# icehax40.net
KiCad netlist of a schematic drawn in EAGLE
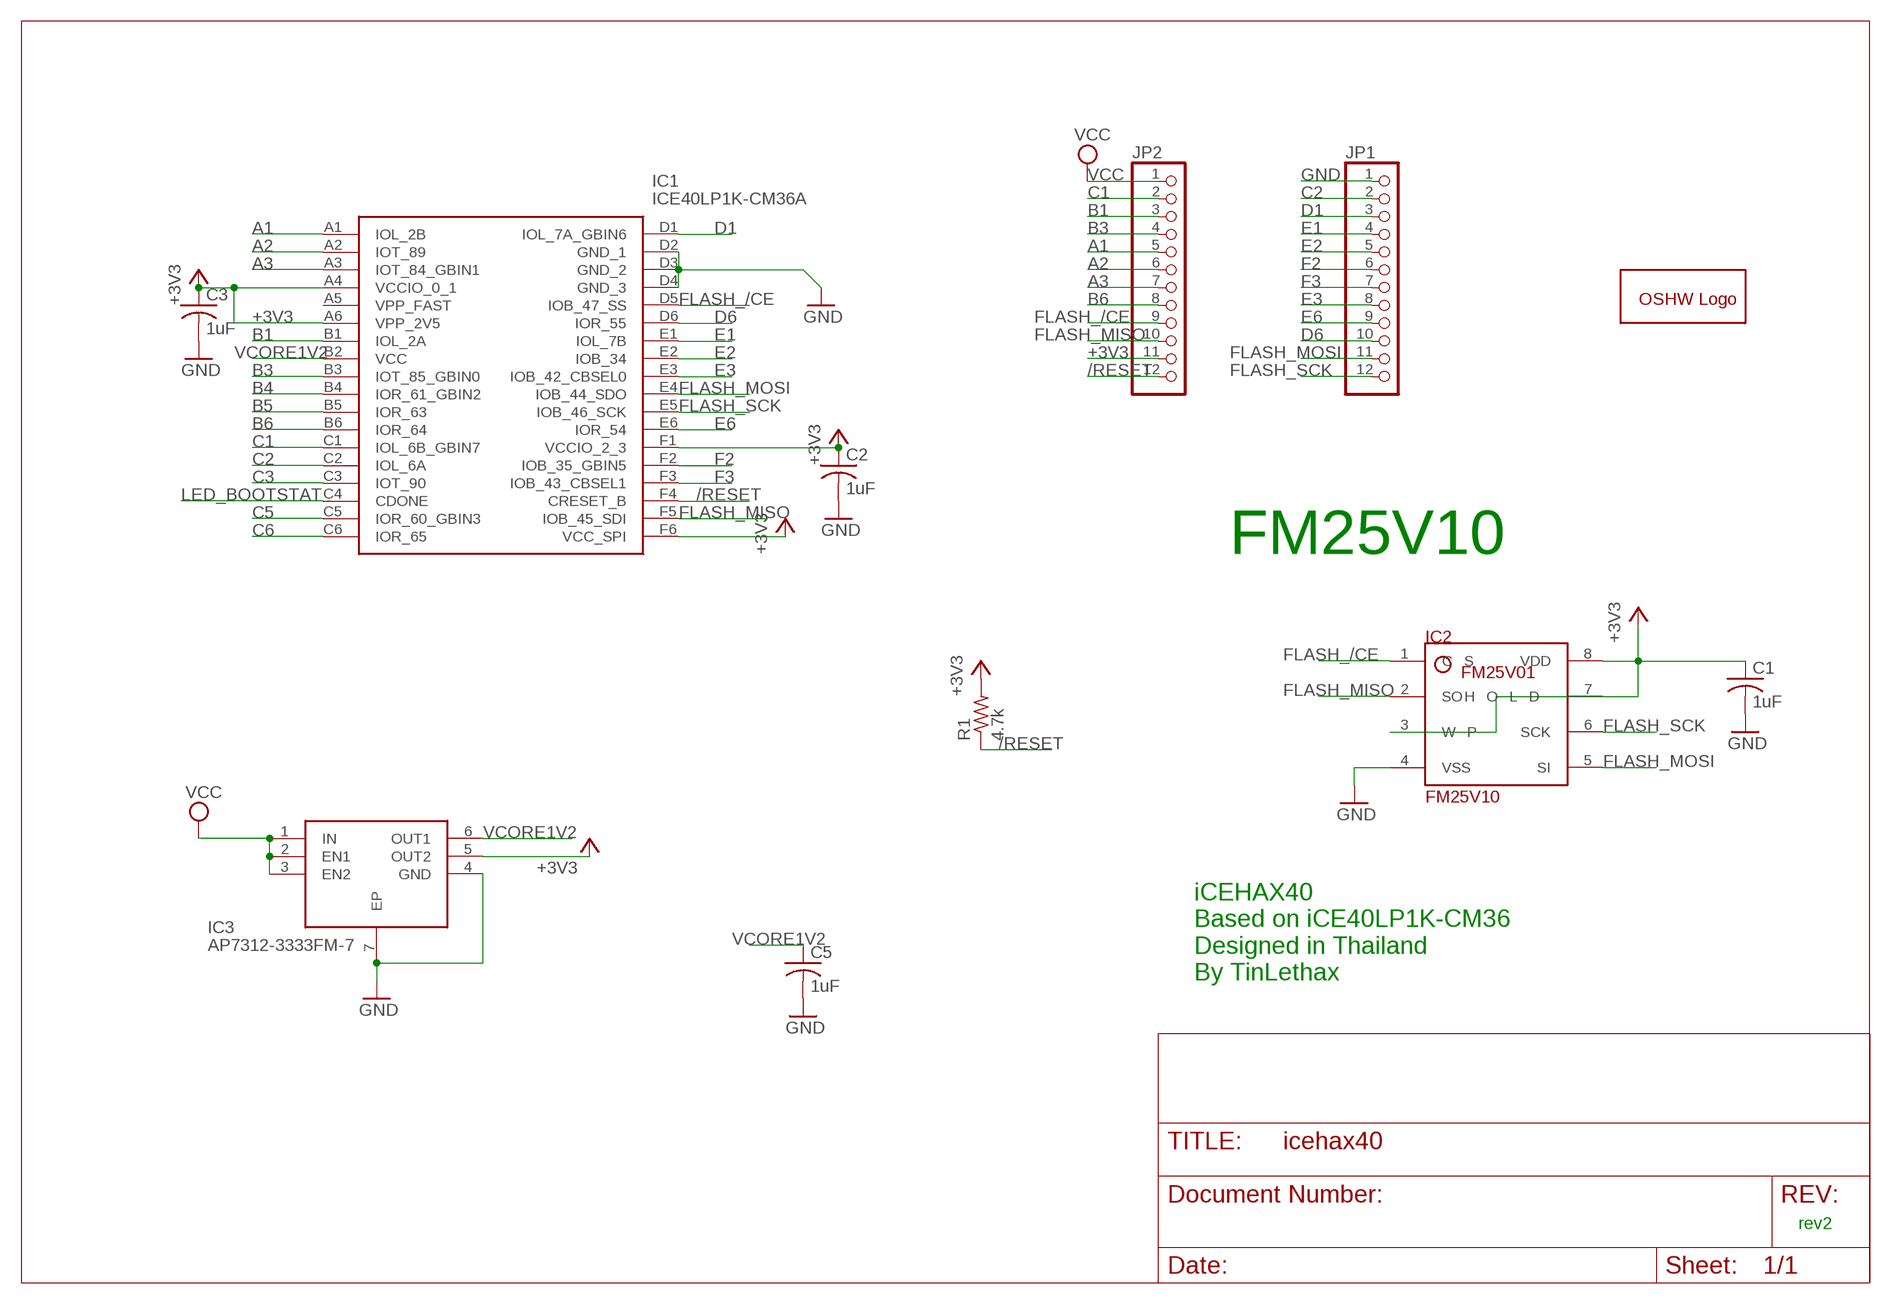
[diagram p0: schematic, sheet 1]

(export (version "E")
  (design (tool "Eeschema 10.0.6"))
  (components
    (comp (ref "C1")
      (value "1uF")
      (footprint "eagle-import:C0603")
      (libsource (lib "eagle-import") (part "C-USC0603"))
    )
    (comp (ref "C2")
      (value "1uF")
      (footprint "eagle-import:C0603")
      (libsource (lib "eagle-import") (part "C-USC0603"))
    )
    (comp (ref "C3")
      (value "1uF")
      (footprint "eagle-import:C0603")
      (libsource (lib "eagle-import") (part "C-USC0603"))
    )
    (comp (ref "C5")
      (value "1uF")
      (footprint "eagle-import:C0603")
      (libsource (lib "eagle-import") (part "C-USC0603"))
    )
    (comp (ref "GOLD_ORB_SM1")
      (value "OSHWLOGOLOGO5MM")
      (footprint "eagle-import:OSHW_5MM")
      (libsource (lib "eagle-import") (part "OSHWLOGOLOGO5MM"))
    )
    (comp (ref "IC1")
      (value "ICE40LP1K-CM36A")
      (footprint "eagle-import:BGA36C40P6X6_250X250X100")
      (fields (field (name "MOUSER_PART_NUMBER") "842-ICE40LP1K-CM36A"))
      (libsource (lib "eagle-import") (part "ICE40LP1K-CM36A"))
    )
    (comp (ref "IC2")
      (value "FM25V10")
      (footprint "eagle-import:SOIC127P601X172-8N")
      (fields (field (name "PARTNO") "FM52V01"))
      (libsource (lib "eagle-import") (part "FM25V01"))
    )
    (comp (ref "IC3")
      (value "AP7312-3333FM-7")
      (footprint "eagle-import:SON50P201X181X60-7N")
      (fields (field (name "MOUSER_PART_NUMBER") "621-AP7312-3333FM-7"))
      (libsource (lib "eagle-import") (part "AP7312-3333FM-7"))
    )
    (comp (ref "JP1")
      (value "PINHD-1X12")
      (footprint "eagle-import:1X12")
      (libsource (lib "eagle-import") (part "PINHD-1X12"))
    )
    (comp (ref "JP2")
      (value "PINHD-1X12")
      (footprint "eagle-import:1X12")
      (libsource (lib "eagle-import") (part "PINHD-1X12"))
    )
    (comp (ref "R1")
      (value "4.7k")
      (footprint "eagle-import:R0603")
      (libsource (lib "eagle-import") (part "R-US_R0603"))
    )
  )
  (nets
    (net (code "1") (name "+3V3") (class "Default")
      (node (ref "C1") (pin "1") (pinfunction "1_1") (pintype "passive"))
      (node (ref "C2") (pin "1") (pinfunction "1_1") (pintype "passive"))
      (node (ref "C3") (pin "1") (pinfunction "1_1") (pintype "passive"))
      (node (ref "IC1") (pin "A4") (pinfunction "VCCIO_0_1_A4") (pintype "bidirectional"))
      (node (ref "IC1") (pin "A6") (pinfunction "VPP_2V5_A6") (pintype "bidirectional"))
      (node (ref "IC1") (pin "F1") (pinfunction "VCCIO_2_3_F1") (pintype "bidirectional"))
      (node (ref "IC1") (pin "F6") (pinfunction "VCC_SPI_F6") (pintype "bidirectional"))
      (node (ref "IC2") (pin "3") (pinfunction "W̅P̅_3") (pintype "bidirectional"))
      (node (ref "IC2") (pin "7") (pinfunction "H̅O̅L̅D̅_7") (pintype "bidirectional"))
      (node (ref "IC2") (pin "8") (pinfunction "VDD_8") (pintype "bidirectional"))
      (node (ref "IC3") (pin "5") (pinfunction "OUT2_5") (pintype "bidirectional"))
      (node (ref "JP2") (pin "11") (pinfunction "11_11") (pintype "passive"))
      (node (ref "R1") (pin "2") (pinfunction "2_2") (pintype "passive"))
    )
    (net (code "2") (name "/A1") (class "Default")
      (node (ref "IC1") (pin "A1") (pinfunction "IOL_2B_A1") (pintype "bidirectional"))
      (node (ref "JP2") (pin "5") (pinfunction "5_5") (pintype "passive"))
    )
    (net (code "3") (name "/A2") (class "Default")
      (node (ref "IC1") (pin "A2") (pinfunction "IOT_89_A2") (pintype "bidirectional"))
      (node (ref "JP2") (pin "6") (pinfunction "6_6") (pintype "passive"))
    )
    (net (code "4") (name "/A3") (class "Default")
      (node (ref "IC1") (pin "A3") (pinfunction "IOT_84_GBIN1_A3") (pintype "bidirectional"))
      (node (ref "JP2") (pin "7") (pinfunction "7_7") (pintype "passive"))
    )
    (net (code "5") (name "/B1") (class "Default")
      (node (ref "IC1") (pin "B1") (pinfunction "IOL_2A_B1") (pintype "bidirectional"))
      (node (ref "JP2") (pin "3") (pinfunction "3_3") (pintype "passive"))
    )
    (net (code "6") (name "/B3") (class "Default")
      (node (ref "IC1") (pin "B3") (pinfunction "IOT_85_GBIN0_B3") (pintype "bidirectional"))
      (node (ref "JP2") (pin "4") (pinfunction "4_4") (pintype "passive"))
    )
    (net (code "7") (name "/B4") (class "Default")
      (node (ref "IC1") (pin "B4") (pinfunction "IOR_61_GBIN2_B4") (pintype "bidirectional"))
    )
    (net (code "8") (name "/B5") (class "Default")
      (node (ref "IC1") (pin "B5") (pinfunction "IOR_63_B5") (pintype "bidirectional"))
    )
    (net (code "9") (name "/B6") (class "Default")
      (node (ref "IC1") (pin "B6") (pinfunction "IOR_64_B6") (pintype "bidirectional"))
      (node (ref "JP2") (pin "8") (pinfunction "8_8") (pintype "passive"))
    )
    (net (code "10") (name "/C1") (class "Default")
      (node (ref "IC1") (pin "C1") (pinfunction "IOL_6B_GBIN7_C1") (pintype "bidirectional"))
      (node (ref "JP2") (pin "2") (pinfunction "2_2") (pintype "passive"))
    )
    (net (code "11") (name "/C2") (class "Default")
      (node (ref "IC1") (pin "C2") (pinfunction "IOL_6A_C2") (pintype "bidirectional"))
      (node (ref "JP1") (pin "2") (pinfunction "2_2") (pintype "passive"))
    )
    (net (code "12") (name "/C3") (class "Default")
      (node (ref "IC1") (pin "C3") (pinfunction "IOT_90_C3") (pintype "bidirectional"))
    )
    (net (code "13") (name "/C5") (class "Default")
      (node (ref "IC1") (pin "C5") (pinfunction "IOR_60_GBIN3_C5") (pintype "bidirectional"))
    )
    (net (code "14") (name "/C6") (class "Default")
      (node (ref "IC1") (pin "C6") (pinfunction "IOR_65_C6") (pintype "bidirectional"))
    )
    (net (code "15") (name "/D1") (class "Default")
      (node (ref "IC1") (pin "D1") (pinfunction "IOL_7A_GBIN6_D1") (pintype "bidirectional"))
      (node (ref "JP1") (pin "3") (pinfunction "3_3") (pintype "passive"))
    )
    (net (code "16") (name "/D6") (class "Default")
      (node (ref "IC1") (pin "D6") (pinfunction "IOR_55_D6") (pintype "bidirectional"))
      (node (ref "JP1") (pin "10") (pinfunction "10_10") (pintype "passive"))
    )
    (net (code "17") (name "/E1") (class "Default")
      (node (ref "IC1") (pin "E1") (pinfunction "IOL_7B_E1") (pintype "bidirectional"))
      (node (ref "JP1") (pin "4") (pinfunction "4_4") (pintype "passive"))
    )
    (net (code "18") (name "/E2") (class "Default")
      (node (ref "IC1") (pin "E2") (pinfunction "IOB_34_E2") (pintype "bidirectional"))
      (node (ref "JP1") (pin "5") (pinfunction "5_5") (pintype "passive"))
    )
    (net (code "19") (name "/E3") (class "Default")
      (node (ref "IC1") (pin "E3") (pinfunction "IOB_42_CBSEL0_E3") (pintype "bidirectional"))
      (node (ref "JP1") (pin "8") (pinfunction "8_8") (pintype "passive"))
    )
    (net (code "20") (name "/E6") (class "Default")
      (node (ref "IC1") (pin "E6") (pinfunction "IOR_54_E6") (pintype "bidirectional"))
      (node (ref "JP1") (pin "9") (pinfunction "9_9") (pintype "passive"))
    )
    (net (code "21") (name "/F2") (class "Default")
      (node (ref "IC1") (pin "F2") (pinfunction "IOB_35_GBIN5_F2") (pintype "bidirectional"))
      (node (ref "JP1") (pin "6") (pinfunction "6_6") (pintype "passive"))
    )
    (net (code "22") (name "/F3") (class "Default")
      (node (ref "IC1") (pin "F3") (pinfunction "IOB_43_CBSEL1_F3") (pintype "bidirectional"))
      (node (ref "JP1") (pin "7") (pinfunction "7_7") (pintype "passive"))
    )
    (net (code "23") (name "/FLASH_MISO") (class "Default")
      (node (ref "IC1") (pin "F5") (pinfunction "IOB_45_SDI_F5") (pintype "bidirectional"))
      (node (ref "IC2") (pin "2") (pinfunction "SO_2") (pintype "bidirectional"))
      (node (ref "JP2") (pin "10") (pinfunction "10_10") (pintype "passive"))
    )
    (net (code "24") (name "/FLASH_MOSI") (class "Default")
      (node (ref "IC1") (pin "E4") (pinfunction "IOB_44_SDO_E4") (pintype "bidirectional"))
      (node (ref "IC2") (pin "5") (pinfunction "SI_5") (pintype "bidirectional"))
      (node (ref "JP1") (pin "11") (pinfunction "11_11") (pintype "passive"))
    )
    (net (code "25") (name "/FLASH_SCK") (class "Default")
      (node (ref "IC1") (pin "E5") (pinfunction "IOB_46_SCK_E5") (pintype "bidirectional"))
      (node (ref "IC2") (pin "6") (pinfunction "SCK_6") (pintype "bidirectional"))
      (node (ref "JP1") (pin "12") (pinfunction "12_12") (pintype "passive"))
    )
    (net (code "26") (name "/FLASH_{slash}CE") (class "Default")
      (node (ref "IC1") (pin "D5") (pinfunction "IOB_47_SS_D5") (pintype "bidirectional"))
      (node (ref "IC2") (pin "1") (pinfunction "C̅S̅_1") (pintype "bidirectional"))
      (node (ref "JP2") (pin "9") (pinfunction "9_9") (pintype "passive"))
    )
    (net (code "27") (name "/LED_BOOTSTAT") (class "Default")
      (node (ref "IC1") (pin "C4") (pinfunction "CDONE_C4") (pintype "bidirectional"))
    )
    (net (code "28") (name "/VCORE1V2") (class "Default")
      (node (ref "C5") (pin "1") (pinfunction "1_1") (pintype "passive"))
      (node (ref "IC1") (pin "B2") (pinfunction "VCC_B2") (pintype "bidirectional"))
      (node (ref "IC3") (pin "6") (pinfunction "OUT1_6") (pintype "bidirectional"))
    )
    (net (code "29") (name "/{slash}RESET") (class "Default")
      (node (ref "IC1") (pin "F4") (pinfunction "CRESET_B_F4") (pintype "bidirectional"))
      (node (ref "JP2") (pin "12") (pinfunction "12_12") (pintype "passive"))
      (node (ref "R1") (pin "1") (pinfunction "1_1") (pintype "passive"))
    )
    (net (code "30") (name "GND") (class "Default")
      (node (ref "C1") (pin "2") (pinfunction "2_2") (pintype "passive"))
      (node (ref "C2") (pin "2") (pinfunction "2_2") (pintype "passive"))
      (node (ref "C3") (pin "2") (pinfunction "2_2") (pintype "passive"))
      (node (ref "C5") (pin "2") (pinfunction "2_2") (pintype "passive"))
      (node (ref "IC1") (pin "D2") (pinfunction "GND_1_D2") (pintype "bidirectional"))
      (node (ref "IC1") (pin "D3") (pinfunction "GND_2_D3") (pintype "bidirectional"))
      (node (ref "IC1") (pin "D4") (pinfunction "GND_3_D4") (pintype "bidirectional"))
      (node (ref "IC2") (pin "4") (pinfunction "VSS_4") (pintype "bidirectional"))
      (node (ref "IC3") (pin "4") (pinfunction "GND_4") (pintype "bidirectional"))
      (node (ref "IC3") (pin "7") (pinfunction "EP_7") (pintype "bidirectional"))
      (node (ref "JP1") (pin "1") (pinfunction "1_1") (pintype "passive"))
    )
    (net (code "31") (name "VCC") (class "Default")
      (node (ref "IC3") (pin "1") (pinfunction "IN_1") (pintype "bidirectional"))
      (node (ref "IC3") (pin "2") (pinfunction "EN1_2") (pintype "bidirectional"))
      (node (ref "IC3") (pin "3") (pinfunction "EN2_3") (pintype "bidirectional"))
      (node (ref "JP2") (pin "1") (pinfunction "1_1") (pintype "passive"))
    )
    (net (code "32") (name "unconnected-(IC1-VPP_FAST-PadA5)") (class "Default")
      (node (ref "IC1") (pin "A5") (pinfunction "VPP_FAST_A5") (pintype "bidirectional"))
    )
  )
)
